# Sheet3.net
KiCad netlist of a schematic drawn in Altium Designer
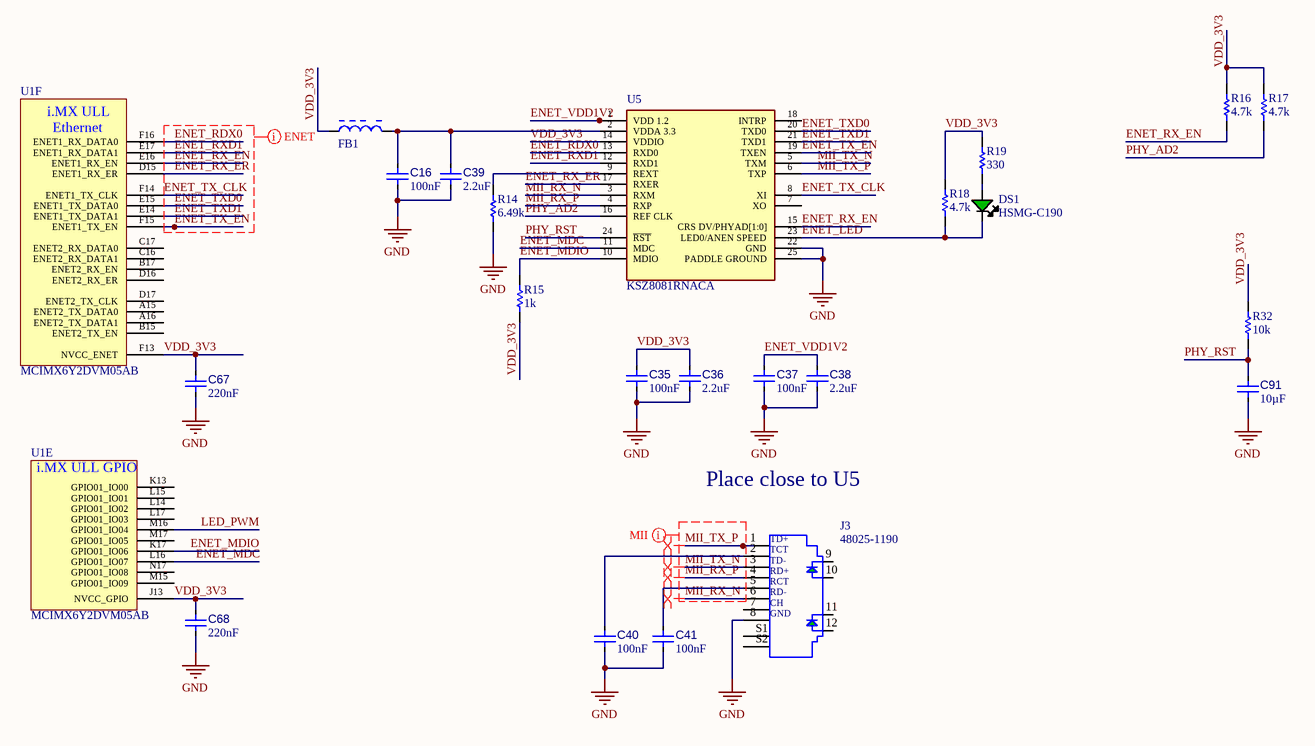
[diagram p0: Sheet3.SchDoc]

(export (version "E")
  (design (tool "Eeschema 10.0.6"))
  (components
    (comp (ref "C16")
      (value "100nF")
      (footprint "0402-SMD-CAP")
      (description "Chip Capacitor, 0.1 uF, +/- 5%, 16 V, 0402 (1005 Metric)")
      (fields (field (name "TOLERANCE") "5%") (field (name "MFR. PART NO.") "EMF105B7104MVHF"))
      (libsource (lib "Budapest University of Technology and Economics") (part "CAP-NP-2"))
    )
    (comp (ref "C35")
      (value "100nF")
      (footprint "0402-SMD-CAP")
      (description "Chip Capacitor, 0.1 uF, +/- 5%, 16 V, 0402 (1005 Metric)")
      (fields (field (name "TOLERANCE") "5%") (field (name "MFR. PART NO.") "EMF105B7104MVHF"))
      (libsource (lib "Budapest University of Technology and Economics") (part "CAP-NP-2"))
    )
    (comp (ref "C36")
      (value "2.2uF")
      (footprint "0603-SMD-CAP")
      (description "CAP CER 2.2UF 10V X7R 0603")
      (fields (field (name "VOLTAGE") "10V") (field (name "TOLERANCE") "10%"))
      (libsource (lib "Budapest University of Technology and Economics") (part "CAP-NP-2"))
    )
    (comp (ref "C37")
      (value "100nF")
      (footprint "0402-SMD-CAP")
      (description "Chip Capacitor, 0.1 uF, +/- 5%, 16 V, 0402 (1005 Metric)")
      (fields (field (name "TOLERANCE") "5%") (field (name "MFR. PART NO.") "EMF105B7104MVHF"))
      (libsource (lib "Budapest University of Technology and Economics") (part "CAP-NP-2"))
    )
    (comp (ref "C38")
      (value "2.2uF")
      (footprint "0603-SMD-CAP")
      (description "CAP CER 2.2UF 10V X7R 0603")
      (fields (field (name "VOLTAGE") "10V") (field (name "TOLERANCE") "10%"))
      (libsource (lib "Budapest University of Technology and Economics") (part "CAP-NP-2"))
    )
    (comp (ref "C39")
      (value "2.2uF")
      (footprint "0603-SMD-CAP")
      (description "CAP CER 2.2UF 10V X7R 0603")
      (fields (field (name "VOLTAGE") "10V") (field (name "TOLERANCE") "10%"))
      (libsource (lib "Budapest University of Technology and Economics") (part "CAP-NP-2"))
    )
    (comp (ref "C40")
      (value "100nF")
      (footprint "0402-SMD-CAP")
      (description "Chip Capacitor, 0.1 uF, +/- 5%, 16 V, 0402 (1005 Metric)")
      (fields (field (name "TOLERANCE") "5%") (field (name "MFR. PART NO.") "EMF105B7104MVHF"))
      (libsource (lib "Budapest University of Technology and Economics") (part "CAP-NP-2"))
    )
    (comp (ref "C41")
      (value "100nF")
      (footprint "0402-SMD-CAP")
      (description "Chip Capacitor, 0.1 uF, +/- 5%, 16 V, 0402 (1005 Metric)")
      (fields (field (name "TOLERANCE") "5%") (field (name "MFR. PART NO.") "EMF105B7104MVHF"))
      (libsource (lib "Budapest University of Technology and Economics") (part "CAP-NP-2"))
    )
    (comp (ref "C67")
      (value "220nF")
      (footprint "0402-SMD-CAP")
      (fields
        (field (name "TOLERANCE") "10%")
        (field (name "VOLTAGE") "16V")
        (field (name "Comment") "GRM155R71C224KA12D")
      )
      (libsource (lib "Budapest University of Technology and Economics") (part "CAP-NP-2"))
    )
    (comp (ref "C68")
      (value "220nF")
      (footprint "0402-SMD-CAP")
      (fields
        (field (name "TOLERANCE") "10%")
        (field (name "VOLTAGE") "16V")
        (field (name "Comment") "GRM155R71C224KA12D")
      )
      (libsource (lib "Budapest University of Technology and Economics") (part "CAP-NP-2"))
    )
    (comp (ref "C91")
      (value "10µF")
      (footprint "0603-SMD-CAP")
      (description "Chip Capacitor, 10µF +/-20%, 10V, 0603, Thickness 1 mm")
      (fields (field (name "TOLERANCE") "10%") (field (name "MFR. PART NO.") "0603ZD106KAT2A"))
      (libsource (lib "Budapest University of Technology and Economics") (part "CAP-NP-2"))
    )
    (comp (ref "DS1")
      (value "HSMG-C190")
      (footprint "AVAG-HSMX-C190_V")
      (description "LED Uni-Color Green, 52 mW, 20 mA, -40 to 85 degC, 2-Pin SMD, RoHS, Tape and Reel")
      (fields (field (name "POWER") "52mW") (field (name "MANUFACTURER") "Avago"))
      (libsource (lib "Budapest University of Technology and Economics") (part "LED-GREEN-AK-2"))
    )
    (comp (ref "FB1")
      (value "BLM21BB221SN1D")
      (footprint "MURA-BLM21-H1-CHIP-2_V")
      (description "FERRITE CHIP 220 OHM 0805")
      (fields (field (name "TOLERANCE") "25%"))
      (libsource (lib "Budapest University of Technology and Economics") (part "MURA-FB-2"))
    )
    (comp (ref "J3")
      (value "48025-1190")
      (footprint "MOLX-48025-1190_V")
      (description "Modular Jack with Integrated Magnetics with LED, 1.5 A, -40 to 70 degC, 12-Pin THD, RoHS, Tray")
      (fields (field (name "MANUFACTURER") "Molex"))
      (libsource (lib "Budapest University of Technology and Economics") (part "RJ45-12-2SHLD_C"))
    )
    (comp (ref "R14")
      (value "6.49k")
      (footprint "0402_SMD_RES")
      (description "Res Thick Film 0402 6.49K Ohm 1% 0.063W(1/16W) ±100ppm/C Pad SMD Automotive T/R")
      (fields (field (name "TOLERANCE") "1%") (field (name "Comment") "CRCW04026K49FKED"))
      (libsource (lib "Budapest University of Technology and Economics") (part "RES-2"))
    )
    (comp (ref "R15")
      (value "1k")
      (footprint "0402_SMD_RES")
      (description "Chip Resistor, 1 KOhm, +/- 1%, 0.1 W, -55 to 155 degC, 0402 (1005 Metric)")
      (fields (field (name "POWER") "100mW") (field (name "TOLERANCE") "1%"))
      (libsource (lib "Budapest University of Technology and Economics") (part "RES-2"))
    )
    (comp (ref "R16")
      (value "4.7k")
      (footprint "0402_SMD_RES")
      (description "Chip Resistor, 4.7 KOhm, +/- 1%, 63 mW, -55 to 155 degC, 0402 (1005 Metric)")
      (fields (field (name "TOLERANCE") "1%") (field (name "POWER") "63mW"))
      (libsource (lib "Budapest University of Technology and Economics") (part "RES-2"))
    )
    (comp (ref "R17")
      (value "4.7k")
      (footprint "0402_SMD_RES")
      (description "Chip Resistor, 4.7 KOhm, +/- 1%, 63 mW, -55 to 155 degC, 0402 (1005 Metric)")
      (fields (field (name "TOLERANCE") "1%") (field (name "POWER") "63mW"))
      (libsource (lib "Budapest University of Technology and Economics") (part "RES-2"))
    )
    (comp (ref "R18")
      (value "4.7k")
      (footprint "0402_SMD_RES")
      (description "Chip Resistor, 4.7 KOhm, +/- 1%, 63 mW, -55 to 155 degC, 0402 (1005 Metric)")
      (fields (field (name "TOLERANCE") "1%") (field (name "POWER") "63mW"))
      (libsource (lib "Budapest University of Technology and Economics") (part "RES-2"))
    )
    (comp (ref "R19")
      (value "330")
      (footprint "0402_SMD_RES")
      (description "Chip Resistor, 330 Ohms, +/-5 %, 63 mW, -55 to 155 degC, 0402")
      (fields (field (name "POWER") "63mW") (field (name "TOLERANCE") "5%"))
      (libsource (lib "Budapest University of Technology and Economics") (part "RES-2"))
    )
    (comp (ref "R32")
      (value "10k")
      (footprint "0402_SMD_RES")
      (description "Chip Resistor, 10 kOhms, +/-1 %, 63 mW, -55 to 125 degC, 0402")
      (fields (field (name "POWER") "63mW") (field (name "TOLERANCE") "1%"))
      (libsource (lib "Budapest University of Technology and Economics") (part "RES-2"))
    )
    (comp (ref "U1")
      (value "MCIMX6Y2DVM05AB")
      (footprint "BGA100P9X9-81A")
      (libsource (lib "Budapest University of Technology and Economics") (part "MCIMX6Y2DVM05AB"))
    )
    (comp (ref "U5")
      (value "KSZ8081RNACA")
      (footprint "FP-QFN44-24LD-PL-1-IPC_C")
      (description "MICROCHIP - KSZ8081RNACA - ETHERNET TRANSCEIVER, 100MBPS, QFN-24")
      (libsource (lib "Budapest University of Technology and Economics") (part "d7667ed9ac825c5f10b2cfcdfaf373b"))
    )
  )
  (nets
    (net (code "1") (name "/ENET_LED") (class "Default")
      (node (ref "DS1") (pin "2") (pinfunction "K_2") (pintype "passive"))
      (node (ref "R18") (pin "1") (pinfunction "1_1") (pintype "passive"))
      (node (ref "U5") (pin "23") (pinfunction "LED0/ANEN_SPEED_23") (pintype "passive"))
    )
    (net (code "2") (name "/ENET_MDC") (class "Default")
      (node (ref "U1") (pin "L16") (pinfunction "GPIO01_IO07_L16") (pintype "passive"))
      (node (ref "U5") (pin "11") (pinfunction "MDC_11") (pintype "passive"))
    )
    (net (code "3") (name "/ENET_MDIO") (class "Default")
      (node (ref "R15") (pin "2") (pinfunction "2_2") (pintype "passive"))
      (node (ref "U1") (pin "K17") (pinfunction "GPIO01_IO06_K17") (pintype "passive"))
      (node (ref "U5") (pin "10") (pinfunction "MDIO_10") (pintype "passive"))
    )
    (net (code "4") (name "/ENET_RDX0") (class "Default")
      (node (ref "U1") (pin "F16") (pinfunction "ENET1_RX_DATA0_F16") (pintype "passive"))
      (node (ref "U5") (pin "13") (pinfunction "RXD0_13") (pintype "passive"))
    )
    (net (code "5") (name "/ENET_RXD1") (class "Default")
      (node (ref "U1") (pin "E17") (pinfunction "ENET1_RX_DATA1_E17") (pintype "passive"))
      (node (ref "U5") (pin "12") (pinfunction "RXD1_12") (pintype "passive"))
    )
    (net (code "6") (name "/ENET_RX_EN") (class "Default")
      (node (ref "R16") (pin "1") (pinfunction "1_1") (pintype "passive"))
      (node (ref "U1") (pin "E16") (pinfunction "ENET1_RX_EN_E16") (pintype "passive"))
      (node (ref "U5") (pin "15") (pinfunction "CRS_DV/PHYAD[1:0]_15") (pintype "passive"))
    )
    (net (code "7") (name "/ENET_RX_ER") (class "Default")
      (node (ref "U1") (pin "D15") (pinfunction "ENET1_RX_ER_D15") (pintype "passive"))
      (node (ref "U5") (pin "17") (pinfunction "RXER_17") (pintype "passive"))
    )
    (net (code "8") (name "/ENET_TXD0") (class "Default")
      (node (ref "U1") (pin "E15") (pinfunction "ENET1_TX_DATA0_E15") (pintype "passive"))
      (node (ref "U5") (pin "20") (pinfunction "TXD0_20") (pintype "passive"))
    )
    (net (code "9") (name "/ENET_TXD1") (class "Default")
      (node (ref "U1") (pin "E14") (pinfunction "ENET1_TX_DATA1_E14") (pintype "passive"))
      (node (ref "U5") (pin "21") (pinfunction "TXD1_21") (pintype "passive"))
    )
    (net (code "10") (name "/ENET_TX_CLK") (class "Default")
      (node (ref "U1") (pin "F14") (pinfunction "ENET1_TX_CLK_F14") (pintype "passive"))
      (node (ref "U5") (pin "8") (pinfunction "XI_8") (pintype "passive"))
    )
    (net (code "11") (name "/ENET_TX_EN") (class "Default")
      (node (ref "U1") (pin "F15") (pinfunction "ENET1_TX_EN_F15") (pintype "passive"))
      (node (ref "U5") (pin "19") (pinfunction "TXEN_19") (pintype "passive"))
    )
    (net (code "12") (name "/ENET_VDD1V2") (class "Default")
      (node (ref "C37") (pin "2") (pinfunction "2_2") (pintype "passive"))
      (node (ref "C38") (pin "2") (pinfunction "2_2") (pintype "passive"))
      (node (ref "U5") (pin "1") (pinfunction "VDD_1.2_1") (pintype "power_in"))
    )
    (net (code "13") (name "/LED_PWM") (class "Default")
      (node (ref "U1") (pin "M16") (pinfunction "GPIO01_IO04_M16") (pintype "passive"))
    )
    (net (code "14") (name "/MII_RX_N") (class "Default")
      (node (ref "J3") (pin "6") (pinfunction "RD-_6") (pintype "passive"))
      (node (ref "U5") (pin "3") (pinfunction "RXM_3") (pintype "passive"))
    )
    (net (code "15") (name "/MII_RX_P") (class "Default")
      (node (ref "J3") (pin "4") (pinfunction "RD+_4") (pintype "passive"))
      (node (ref "U5") (pin "4") (pinfunction "RXP_4") (pintype "passive"))
    )
    (net (code "16") (name "/MII_TX_N") (class "Default")
      (node (ref "J3") (pin "3") (pinfunction "TD-_3") (pintype "passive"))
      (node (ref "U5") (pin "5") (pinfunction "TXM_5") (pintype "passive"))
    )
    (net (code "17") (name "/MII_TX_P") (class "Default")
      (node (ref "J3") (pin "1") (pinfunction "TD+_1") (pintype "passive"))
      (node (ref "U5") (pin "6") (pinfunction "TXP_6") (pintype "passive"))
    )
    (net (code "18") (name "/PHY_AD2") (class "Default")
      (node (ref "R17") (pin "1") (pinfunction "1_1") (pintype "passive"))
      (node (ref "U5") (pin "16") (pinfunction "REF_CLK_16") (pintype "passive"))
    )
    (net (code "19") (name "/PHY_RST") (class "Default")
      (node (ref "C91") (pin "1") (pinfunction "1_1") (pintype "passive"))
      (node (ref "R32") (pin "1") (pinfunction "1_1") (pintype "passive"))
      (node (ref "U5") (pin "24") (pinfunction "~{RST}_24") (pintype "passive"))
    )
    (net (code "20") (name "/VDD_3V3") (class "Default")
      (node (ref "C35") (pin "2") (pinfunction "2_2") (pintype "passive"))
      (node (ref "C36") (pin "2") (pinfunction "2_2") (pintype "passive"))
      (node (ref "C67") (pin "1") (pinfunction "1_1") (pintype "passive"))
      (node (ref "C68") (pin "1") (pinfunction "1_1") (pintype "passive"))
      (node (ref "FB1") (pin "1") (pinfunction "1_1") (pintype "passive"))
      (node (ref "R15") (pin "1") (pinfunction "1_1") (pintype "passive"))
      (node (ref "R16") (pin "2") (pinfunction "2_2") (pintype "passive"))
      (node (ref "R17") (pin "2") (pinfunction "2_2") (pintype "passive"))
      (node (ref "R18") (pin "2") (pinfunction "2_2") (pintype "passive"))
      (node (ref "R19") (pin "2") (pinfunction "2_2") (pintype "passive"))
      (node (ref "R32") (pin "2") (pinfunction "2_2") (pintype "passive"))
      (node (ref "U1") (pin "F13") (pinfunction "NVCC_ENET_F13") (pintype "passive"))
      (node (ref "U1") (pin "J13") (pinfunction "NVCC_GPIO_J13") (pintype "passive"))
      (node (ref "U5") (pin "14") (pinfunction "VDDIO_14") (pintype "power_in"))
    )
    (net (code "21") (name "GND") (class "Default")
      (node (ref "C16") (pin "1") (pinfunction "1_1") (pintype "passive"))
      (node (ref "C35") (pin "1") (pinfunction "1_1") (pintype "passive"))
      (node (ref "C36") (pin "1") (pinfunction "1_1") (pintype "passive"))
      (node (ref "C37") (pin "1") (pinfunction "1_1") (pintype "passive"))
      (node (ref "C38") (pin "1") (pinfunction "1_1") (pintype "passive"))
      (node (ref "C39") (pin "1") (pinfunction "1_1") (pintype "passive"))
      (node (ref "C40") (pin "1") (pinfunction "1_1") (pintype "passive"))
      (node (ref "C41") (pin "1") (pinfunction "1_1") (pintype "passive"))
      (node (ref "C67") (pin "2") (pinfunction "2_2") (pintype "passive"))
      (node (ref "C68") (pin "2") (pinfunction "2_2") (pintype "passive"))
      (node (ref "C91") (pin "2") (pinfunction "2_2") (pintype "passive"))
      (node (ref "J3") (pin "8") (pinfunction "GND_8") (pintype "passive"))
      (node (ref "R14") (pin "1") (pinfunction "1_1") (pintype "passive"))
      (node (ref "U5") (pin "22") (pinfunction "GND_22") (pintype "power_in"))
      (node (ref "U5") (pin "25") (pinfunction "PADDLE_GROUND_25") (pintype "power_in"))
    )
    (net (code "22") (name "Net-(DS1-A)") (class "Default")
      (node (ref "DS1") (pin "1") (pinfunction "A_1") (pintype "passive"))
      (node (ref "R19") (pin "1") (pinfunction "1_1") (pintype "passive"))
    )
    (net (code "23") (name "Net-(J3-RCT)") (class "Default")
      (node (ref "C41") (pin "2") (pinfunction "2_2") (pintype "passive"))
      (node (ref "J3") (pin "5") (pinfunction "RCT_5") (pintype "passive"))
    )
    (net (code "24") (name "Net-(J3-TCT)") (class "Default")
      (node (ref "C40") (pin "2") (pinfunction "2_2") (pintype "passive"))
      (node (ref "J3") (pin "2") (pinfunction "TCT_2") (pintype "passive"))
    )
    (net (code "25") (name "Net-(U5-REXT)") (class "Default")
      (node (ref "R14") (pin "2") (pinfunction "2_2") (pintype "passive"))
      (node (ref "U5") (pin "9") (pinfunction "REXT_9") (pintype "passive"))
    )
    (net (code "26") (name "Net-(U5-VDDA_3.3)") (class "Default")
      (node (ref "C16") (pin "2") (pinfunction "2_2") (pintype "passive"))
      (node (ref "C39") (pin "2") (pinfunction "2_2") (pintype "passive"))
      (node (ref "FB1") (pin "2") (pinfunction "2_2") (pintype "passive"))
      (node (ref "U5") (pin "2") (pinfunction "VDDA_3.3_2") (pintype "power_in"))
    )
    (net (code "27") (name "unconnected-(J3-CHASSIS-Pad7)") (class "Default")
      (node (ref "J3") (pin "7") (pinfunction "CHASSIS_7") (pintype "passive"))
    )
    (net (code "28") (name "unconnected-(J3-Pad9)") (class "Default")
      (node (ref "J3") (pin "9") (pinfunction "9_9") (pintype "passive"))
    )
    (net (code "29") (name "unconnected-(J3-Pad10)") (class "Default")
      (node (ref "J3") (pin "10") (pinfunction "10_10") (pintype "passive"))
    )
    (net (code "30") (name "unconnected-(J3-Pad11)") (class "Default")
      (node (ref "J3") (pin "11") (pinfunction "11_11") (pintype "passive"))
    )
    (net (code "31") (name "unconnected-(J3-Pad12)") (class "Default")
      (node (ref "J3") (pin "12") (pinfunction "12_12") (pintype "passive"))
    )
    (net (code "32") (name "unconnected-(J3-PadS1)") (class "Default")
      (node (ref "J3") (pin "S1") (pinfunction "S1_S1") (pintype "passive"))
    )
    (net (code "33") (name "unconnected-(J3-PadS2)") (class "Default")
      (node (ref "J3") (pin "S2") (pinfunction "S2_S2") (pintype "passive"))
    )
    (net (code "34") (name "unconnected-(U1E-GPIO01_IO00-PadK13)") (class "Default")
      (node (ref "U1") (pin "K13") (pinfunction "GPIO01_IO00_K13") (pintype "passive"))
    )
    (net (code "35") (name "unconnected-(U1E-GPIO01_IO01-PadL15)") (class "Default")
      (node (ref "U1") (pin "L15") (pinfunction "GPIO01_IO01_L15") (pintype "passive"))
    )
    (net (code "36") (name "unconnected-(U1E-GPIO01_IO02-PadL14)") (class "Default")
      (node (ref "U1") (pin "L14") (pinfunction "GPIO01_IO02_L14") (pintype "passive"))
    )
    (net (code "37") (name "unconnected-(U1E-GPIO01_IO03-PadL17)") (class "Default")
      (node (ref "U1") (pin "L17") (pinfunction "GPIO01_IO03_L17") (pintype "passive"))
    )
    (net (code "38") (name "unconnected-(U1E-GPIO01_IO05-PadM17)") (class "Default")
      (node (ref "U1") (pin "M17") (pinfunction "GPIO01_IO05_M17") (pintype "passive"))
    )
    (net (code "39") (name "unconnected-(U1E-GPIO01_IO08-PadN17)") (class "Default")
      (node (ref "U1") (pin "N17") (pinfunction "GPIO01_IO08_N17") (pintype "passive"))
    )
    (net (code "40") (name "unconnected-(U1E-GPIO01_IO09-PadM15)") (class "Default")
      (node (ref "U1") (pin "M15") (pinfunction "GPIO01_IO09_M15") (pintype "passive"))
    )
    (net (code "41") (name "unconnected-(U1F-ENET2_RX_DATA0-PadC17)") (class "Default")
      (node (ref "U1") (pin "C17") (pinfunction "ENET2_RX_DATA0_C17") (pintype "passive"))
    )
    (net (code "42") (name "unconnected-(U1F-ENET2_RX_DATA1-PadC16)") (class "Default")
      (node (ref "U1") (pin "C16") (pinfunction "ENET2_RX_DATA1_C16") (pintype "passive"))
    )
    (net (code "43") (name "unconnected-(U1F-ENET2_RX_EN-PadB17)") (class "Default")
      (node (ref "U1") (pin "B17") (pinfunction "ENET2_RX_EN_B17") (pintype "passive"))
    )
    (net (code "44") (name "unconnected-(U1F-ENET2_RX_ER-PadD16)") (class "Default")
      (node (ref "U1") (pin "D16") (pinfunction "ENET2_RX_ER_D16") (pintype "passive"))
    )
    (net (code "45") (name "unconnected-(U1F-ENET2_TX_CLK-PadD17)") (class "Default")
      (node (ref "U1") (pin "D17") (pinfunction "ENET2_TX_CLK_D17") (pintype "passive"))
    )
    (net (code "46") (name "unconnected-(U1F-ENET2_TX_DATA0-PadA15)") (class "Default")
      (node (ref "U1") (pin "A15") (pinfunction "ENET2_TX_DATA0_A15") (pintype "passive"))
    )
    (net (code "47") (name "unconnected-(U1F-ENET2_TX_DATA1-PadA16)") (class "Default")
      (node (ref "U1") (pin "A16") (pinfunction "ENET2_TX_DATA1_A16") (pintype "passive"))
    )
    (net (code "48") (name "unconnected-(U1F-ENET2_TX_EN-PadB15)") (class "Default")
      (node (ref "U1") (pin "B15") (pinfunction "ENET2_TX_EN_B15") (pintype "passive"))
    )
    (net (code "49") (name "unconnected-(U5-INTRP-Pad18)") (class "Default")
      (node (ref "U5") (pin "18") (pinfunction "INTRP_18") (pintype "passive"))
    )
    (net (code "50") (name "unconnected-(U5-XO-Pad7)") (class "Default")
      (node (ref "U5") (pin "7") (pinfunction "XO_7") (pintype "passive"))
    )
  )
)
